# D18_1_0.net
KiCad netlist of a schematic drawn in EAGLE
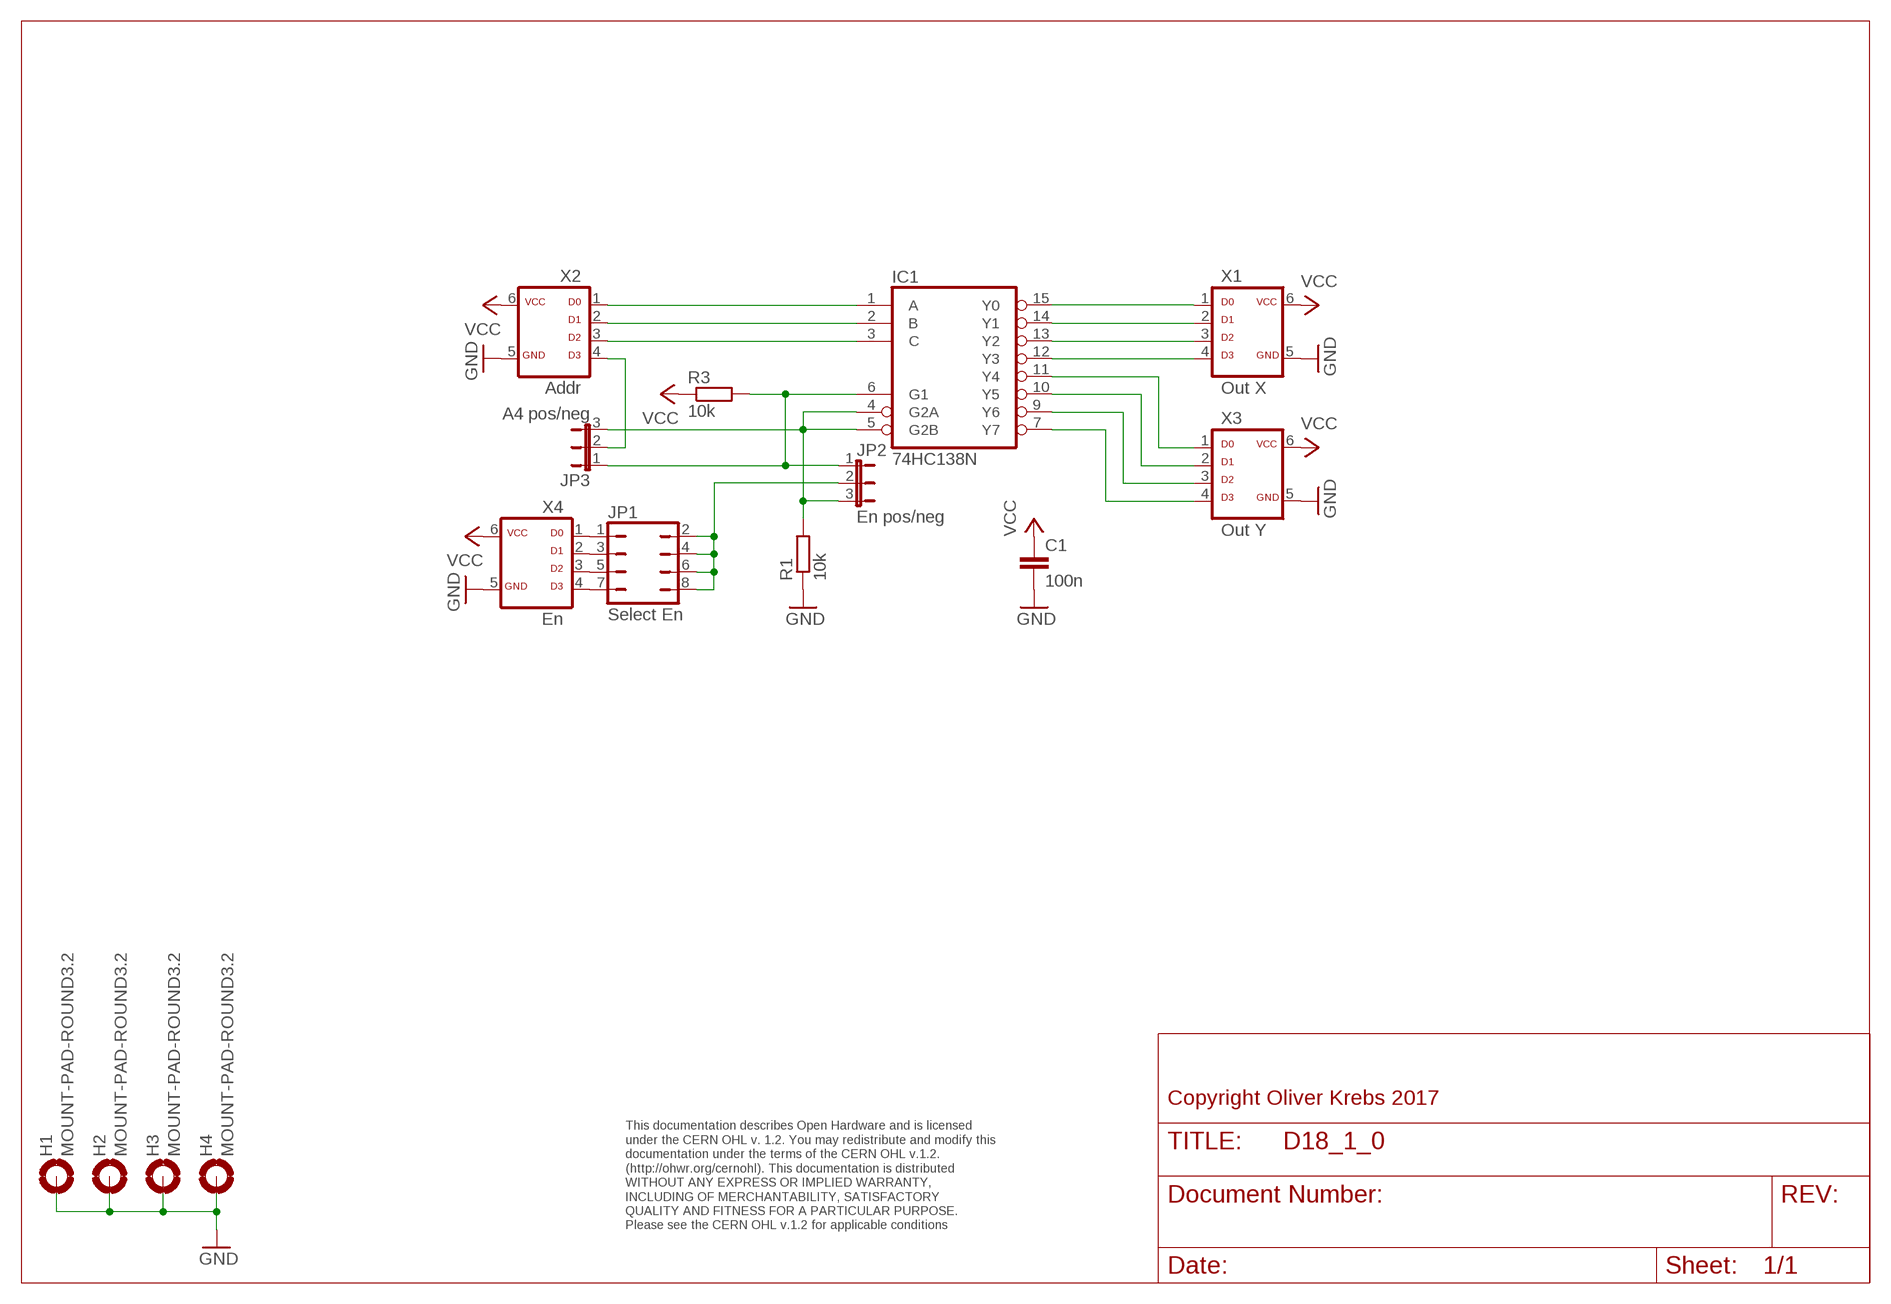
[diagram p0: schematic, sheet 1]

(export (version "E")
  (design (tool "Eeschema 10.0.6"))
  (components
    (comp (ref "C1")
      (value "100n")
      (footprint "eagle-import:C050-025X075")
      (libsource (lib "eagle-import") (part "C-EU050-025X075"))
    )
    (comp (ref "H1")
      (value "MOUNT-PAD-ROUND3.2")
      (footprint "eagle-import:3,2-PAD")
      (libsource (lib "eagle-import") (part "MOUNT-PAD-ROUND3.2"))
    )
    (comp (ref "H2")
      (value "MOUNT-PAD-ROUND3.2")
      (footprint "eagle-import:3,2-PAD")
      (libsource (lib "eagle-import") (part "MOUNT-PAD-ROUND3.2"))
    )
    (comp (ref "H3")
      (value "MOUNT-PAD-ROUND3.2")
      (footprint "eagle-import:3,2-PAD")
      (libsource (lib "eagle-import") (part "MOUNT-PAD-ROUND3.2"))
    )
    (comp (ref "H4")
      (value "MOUNT-PAD-ROUND3.2")
      (footprint "eagle-import:3,2-PAD")
      (libsource (lib "eagle-import") (part "MOUNT-PAD-ROUND3.2"))
    )
    (comp (ref "IC1")
      (value "74HC138N")
      (footprint "eagle-import:DIL16")
      (libsource (lib "eagle-import") (part "74138NHC"))
    )
    (comp (ref "JP1")
      (value "Select En")
      (footprint "eagle-import:JP4Q")
      (libsource (lib "eagle-import") (part "JP4Q"))
    )
    (comp (ref "JP2")
      (value "En pos/neg")
      (footprint "eagle-import:JP2-U")
      (libsource (lib "eagle-import") (part "JP2EJP2-U"))
    )
    (comp (ref "JP3")
      (value "A4 pos/neg")
      (footprint "eagle-import:JP2-U")
      (libsource (lib "eagle-import") (part "JP2EJP2-U"))
    )
    (comp (ref "R1")
      (value "10k")
      (footprint "eagle-import:0207_10")
      (libsource (lib "eagle-import") (part "R-EU_0207/10"))
    )
    (comp (ref "R3")
      (value "10k")
      (footprint "eagle-import:0207_10")
      (libsource (lib "eagle-import") (part "R-EU_0207/10"))
    )
    (comp (ref "X1")
      (value "Out X")
      (footprint "eagle-import:ML-6")
      (libsource (lib "eagle-import") (part "ML6D"))
    )
    (comp (ref "X2")
      (value "Addr")
      (footprint "eagle-import:ML-6")
      (libsource (lib "eagle-import") (part "ML6D"))
    )
    (comp (ref "X3")
      (value "Out Y")
      (footprint "eagle-import:ML-6")
      (libsource (lib "eagle-import") (part "ML6D"))
    )
    (comp (ref "X4")
      (value "En")
      (footprint "eagle-import:ML-6")
      (libsource (lib "eagle-import") (part "ML6D"))
    )
  )
  (nets
    (net (code "1") (name "GND") (class "Default")
      (node (ref "C1") (pin "2") (pinfunction "2_2") (pintype "passive"))
      (node (ref "H1") (pin "B3,2") (pinfunction "MOUNT_B3,2") (pintype "passive"))
      (node (ref "H2") (pin "B3,2") (pinfunction "MOUNT_B3,2") (pintype "passive"))
      (node (ref "H3") (pin "B3,2") (pinfunction "MOUNT_B3,2") (pintype "passive"))
      (node (ref "H4") (pin "B3,2") (pinfunction "MOUNT_B3,2") (pintype "passive"))
      (node (ref "R1") (pin "1") (pinfunction "1_1") (pintype "passive"))
      (node (ref "X1") (pin "5") (pinfunction "5_5") (pintype "passive"))
      (node (ref "X2") (pin "5") (pinfunction "5_5") (pintype "passive"))
      (node (ref "X3") (pin "5") (pinfunction "5_5") (pintype "passive"))
      (node (ref "X4") (pin "5") (pinfunction "5_5") (pintype "passive"))
    )
    (net (code "2") (name "Net-(IC1A-A)") (class "Default")
      (node (ref "IC1") (pin "1") (pinfunction "A_1") (pintype "input"))
      (node (ref "X2") (pin "1") (pinfunction "1_1") (pintype "passive"))
    )
    (net (code "3") (name "Net-(IC1A-B)") (class "Default")
      (node (ref "IC1") (pin "2") (pinfunction "B_2") (pintype "input"))
      (node (ref "X2") (pin "2") (pinfunction "2_2") (pintype "passive"))
    )
    (net (code "4") (name "Net-(IC1A-C)") (class "Default")
      (node (ref "IC1") (pin "3") (pinfunction "C_3") (pintype "input"))
      (node (ref "X2") (pin "3") (pinfunction "3_3") (pintype "passive"))
    )
    (net (code "5") (name "Net-(IC1A-G1)") (class "Default")
      (node (ref "IC1") (pin "6") (pinfunction "G1_6") (pintype "input"))
      (node (ref "JP2") (pin "1") (pinfunction "1_1") (pintype "passive"))
      (node (ref "JP3") (pin "1") (pinfunction "1_1") (pintype "passive"))
      (node (ref "R3") (pin "2") (pinfunction "2_2") (pintype "passive"))
    )
    (net (code "6") (name "Net-(IC1A-G2A)") (class "Default")
      (node (ref "IC1") (pin "4") (pinfunction "G2A_4") (pintype "input"))
      (node (ref "IC1") (pin "5") (pinfunction "G2B_5") (pintype "input"))
      (node (ref "JP2") (pin "3") (pinfunction "3_3") (pintype "passive"))
      (node (ref "JP3") (pin "3") (pinfunction "3_3") (pintype "passive"))
      (node (ref "R1") (pin "2") (pinfunction "2_2") (pintype "passive"))
    )
    (net (code "7") (name "Net-(IC1A-Y0)") (class "Default")
      (node (ref "IC1") (pin "15") (pinfunction "Y0_15") (pintype "output"))
      (node (ref "X1") (pin "1") (pinfunction "1_1") (pintype "passive"))
    )
    (net (code "8") (name "Net-(IC1A-Y1)") (class "Default")
      (node (ref "IC1") (pin "14") (pinfunction "Y1_14") (pintype "output"))
      (node (ref "X1") (pin "2") (pinfunction "2_2") (pintype "passive"))
    )
    (net (code "9") (name "Net-(IC1A-Y2)") (class "Default")
      (node (ref "IC1") (pin "13") (pinfunction "Y2_13") (pintype "output"))
      (node (ref "X1") (pin "3") (pinfunction "3_3") (pintype "passive"))
    )
    (net (code "10") (name "Net-(IC1A-Y3)") (class "Default")
      (node (ref "IC1") (pin "12") (pinfunction "Y3_12") (pintype "output"))
      (node (ref "X1") (pin "4") (pinfunction "4_4") (pintype "passive"))
    )
    (net (code "11") (name "Net-(IC1A-Y4)") (class "Default")
      (node (ref "IC1") (pin "11") (pinfunction "Y4_11") (pintype "output"))
      (node (ref "X3") (pin "1") (pinfunction "1_1") (pintype "passive"))
    )
    (net (code "12") (name "Net-(IC1A-Y5)") (class "Default")
      (node (ref "IC1") (pin "10") (pinfunction "Y5_10") (pintype "output"))
      (node (ref "X3") (pin "2") (pinfunction "2_2") (pintype "passive"))
    )
    (net (code "13") (name "Net-(IC1A-Y6)") (class "Default")
      (node (ref "IC1") (pin "9") (pinfunction "Y6_9") (pintype "output"))
      (node (ref "X3") (pin "3") (pinfunction "3_3") (pintype "passive"))
    )
    (net (code "14") (name "Net-(IC1A-Y7)") (class "Default")
      (node (ref "IC1") (pin "7") (pinfunction "Y7_7") (pintype "output"))
      (node (ref "X3") (pin "4") (pinfunction "4_4") (pintype "passive"))
    )
    (net (code "15") (name "Net-(JP1-Pad1)") (class "Default")
      (node (ref "JP1") (pin "1") (pinfunction "1_1") (pintype "passive"))
      (node (ref "X4") (pin "1") (pinfunction "1_1") (pintype "passive"))
    )
    (net (code "16") (name "Net-(JP1-Pad2)") (class "Default")
      (node (ref "JP1") (pin "2") (pinfunction "2_2") (pintype "passive"))
      (node (ref "JP1") (pin "4") (pinfunction "4_4") (pintype "passive"))
      (node (ref "JP1") (pin "6") (pinfunction "6_6") (pintype "passive"))
      (node (ref "JP1") (pin "8") (pinfunction "8_8") (pintype "passive"))
      (node (ref "JP2") (pin "2") (pinfunction "2_2") (pintype "passive"))
    )
    (net (code "17") (name "Net-(JP1-Pad3)") (class "Default")
      (node (ref "JP1") (pin "3") (pinfunction "3_3") (pintype "passive"))
      (node (ref "X4") (pin "2") (pinfunction "2_2") (pintype "passive"))
    )
    (net (code "18") (name "Net-(JP1-Pad5)") (class "Default")
      (node (ref "JP1") (pin "5") (pinfunction "5_5") (pintype "passive"))
      (node (ref "X4") (pin "3") (pinfunction "3_3") (pintype "passive"))
    )
    (net (code "19") (name "Net-(JP1-Pad7)") (class "Default")
      (node (ref "JP1") (pin "7") (pinfunction "7_7") (pintype "passive"))
      (node (ref "X4") (pin "4") (pinfunction "4_4") (pintype "passive"))
    )
    (net (code "20") (name "Net-(JP3-Pad2)") (class "Default")
      (node (ref "JP3") (pin "2") (pinfunction "2_2") (pintype "passive"))
      (node (ref "X2") (pin "4") (pinfunction "4_4") (pintype "passive"))
    )
    (net (code "21") (name "VCC") (class "Default")
      (node (ref "C1") (pin "1") (pinfunction "1_1") (pintype "passive"))
      (node (ref "R3") (pin "1") (pinfunction "1_1") (pintype "passive"))
      (node (ref "X1") (pin "6") (pinfunction "6_6") (pintype "passive"))
      (node (ref "X2") (pin "6") (pinfunction "6_6") (pintype "passive"))
      (node (ref "X3") (pin "6") (pinfunction "6_6") (pintype "passive"))
      (node (ref "X4") (pin "6") (pinfunction "6_6") (pintype "passive"))
    )
  )
)
